# sandbox.net
KiCad netlist of a schematic drawn in EAGLE
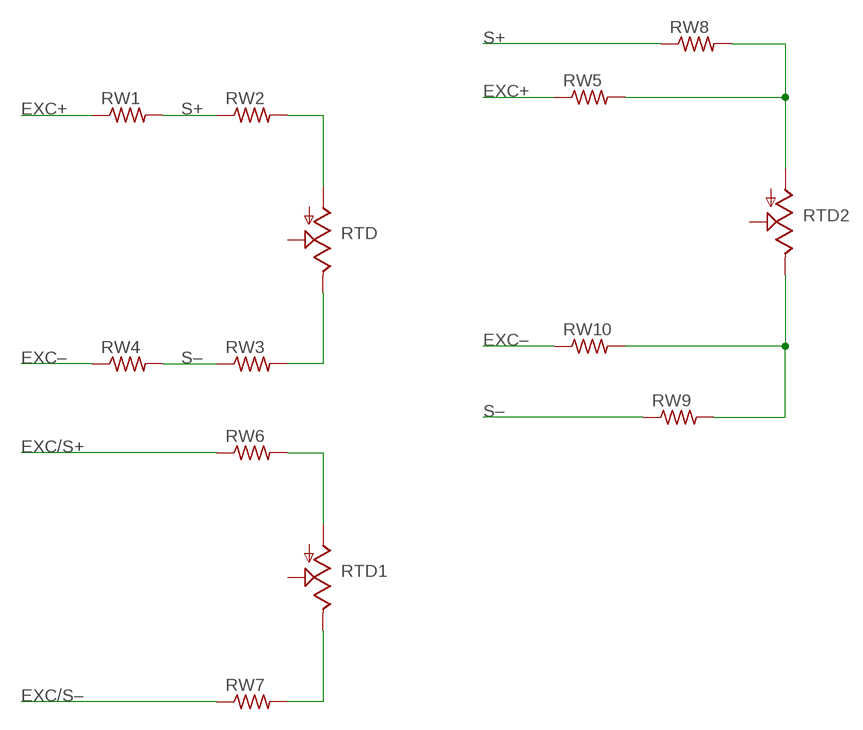
[diagram p0: schematic, sheet 1]

(export (version "E")
  (design (tool "Eeschema 10.0.6"))
  (components
    (comp (ref "RTD")
      (value "TRIM_US-3223G")
      (footprint "eagle-import:3223G")
      (libsource (lib "eagle-import") (part "TRIM_US-3223G"))
    )
    (comp (ref "RTD1")
      (value "TRIM_US-3223G")
      (footprint "eagle-import:3223G")
      (libsource (lib "eagle-import") (part "TRIM_US-3223G"))
    )
    (comp (ref "RTD2")
      (value "TRIM_US-3223G")
      (footprint "eagle-import:3223G")
      (libsource (lib "eagle-import") (part "TRIM_US-3223G"))
    )
    (comp (ref "RW1")
      (value "R-US_R0603")
      (footprint "eagle-import:R0603")
      (libsource (lib "eagle-import") (part "R-US_R0603"))
    )
    (comp (ref "RW2")
      (value "R-US_R0603")
      (footprint "eagle-import:R0603")
      (libsource (lib "eagle-import") (part "R-US_R0603"))
    )
    (comp (ref "RW3")
      (value "R-US_R0603")
      (footprint "eagle-import:R0603")
      (libsource (lib "eagle-import") (part "R-US_R0603"))
    )
    (comp (ref "RW4")
      (value "R-US_R0603")
      (footprint "eagle-import:R0603")
      (libsource (lib "eagle-import") (part "R-US_R0603"))
    )
    (comp (ref "RW5")
      (value "R-US_R0603")
      (footprint "eagle-import:R0603")
      (libsource (lib "eagle-import") (part "R-US_R0603"))
    )
    (comp (ref "RW6")
      (value "R-US_R0603")
      (footprint "eagle-import:R0603")
      (libsource (lib "eagle-import") (part "R-US_R0603"))
    )
    (comp (ref "RW7")
      (value "R-US_R0603")
      (footprint "eagle-import:R0603")
      (libsource (lib "eagle-import") (part "R-US_R0603"))
    )
    (comp (ref "RW8")
      (value "R-US_R0603")
      (footprint "eagle-import:R0603")
      (libsource (lib "eagle-import") (part "R-US_R0603"))
    )
    (comp (ref "RW9")
      (value "R-US_R0603")
      (footprint "eagle-import:R0603")
      (libsource (lib "eagle-import") (part "R-US_R0603"))
    )
    (comp (ref "RW10")
      (value "R-US_R0603")
      (footprint "eagle-import:R0603")
      (libsource (lib "eagle-import") (part "R-US_R0603"))
    )
  )
  (nets
    (net (code "1") (name "/EXC+") (class "Default")
      (node (ref "RW1") (pin "1") (pinfunction "1_1") (pintype "passive"))
      (node (ref "RW5") (pin "1") (pinfunction "1_1") (pintype "passive"))
    )
    (net (code "2") (name "/EXC{slash}S+") (class "Default")
      (node (ref "RW6") (pin "1") (pinfunction "1_1") (pintype "passive"))
    )
    (net (code "3") (name "/EXC{slash}S–") (class "Default")
      (node (ref "RW7") (pin "1") (pinfunction "1_1") (pintype "passive"))
    )
    (net (code "4") (name "/EXC–") (class "Default")
      (node (ref "RW10") (pin "1") (pinfunction "1_1") (pintype "passive"))
      (node (ref "RW4") (pin "1") (pinfunction "1_1") (pintype "passive"))
    )
    (net (code "5") (name "/S+") (class "Default")
      (node (ref "RW1") (pin "2") (pinfunction "2_2") (pintype "passive"))
      (node (ref "RW2") (pin "1") (pinfunction "1_1") (pintype "passive"))
      (node (ref "RW8") (pin "1") (pinfunction "1_1") (pintype "passive"))
    )
    (net (code "6") (name "/S–") (class "Default")
      (node (ref "RW3") (pin "1") (pinfunction "1_1") (pintype "passive"))
      (node (ref "RW4") (pin "2") (pinfunction "2_2") (pintype "passive"))
      (node (ref "RW9") (pin "1") (pinfunction "1_1") (pintype "passive"))
    )
    (net (code "7") (name "Net-(RTD-A)") (class "Default")
      (node (ref "RTD") (pin "1") (pinfunction "A_1") (pintype "passive"))
      (node (ref "RW2") (pin "2") (pinfunction "2_2") (pintype "passive"))
    )
    (net (code "8") (name "Net-(RTD-E)") (class "Default")
      (node (ref "RTD") (pin "3") (pinfunction "E_3") (pintype "passive"))
      (node (ref "RW3") (pin "2") (pinfunction "2_2") (pintype "passive"))
    )
    (net (code "9") (name "Net-(RTD1-A)") (class "Default")
      (node (ref "RTD1") (pin "1") (pinfunction "A_1") (pintype "passive"))
      (node (ref "RW6") (pin "2") (pinfunction "2_2") (pintype "passive"))
    )
    (net (code "10") (name "Net-(RTD1-E)") (class "Default")
      (node (ref "RTD1") (pin "3") (pinfunction "E_3") (pintype "passive"))
      (node (ref "RW7") (pin "2") (pinfunction "2_2") (pintype "passive"))
    )
    (net (code "11") (name "Net-(RTD2-A)") (class "Default")
      (node (ref "RTD2") (pin "1") (pinfunction "A_1") (pintype "passive"))
      (node (ref "RW5") (pin "2") (pinfunction "2_2") (pintype "passive"))
      (node (ref "RW8") (pin "2") (pinfunction "2_2") (pintype "passive"))
    )
    (net (code "12") (name "Net-(RTD2-E)") (class "Default")
      (node (ref "RTD2") (pin "3") (pinfunction "E_3") (pintype "passive"))
      (node (ref "RW10") (pin "2") (pinfunction "2_2") (pintype "passive"))
      (node (ref "RW9") (pin "2") (pinfunction "2_2") (pintype "passive"))
    )
    (net (code "13") (name "unconnected-(RTD-S-Pad2)") (class "Default")
      (node (ref "RTD") (pin "2") (pinfunction "S_2") (pintype "passive"))
    )
    (net (code "14") (name "unconnected-(RTD1-S-Pad2)") (class "Default")
      (node (ref "RTD1") (pin "2") (pinfunction "S_2") (pintype "passive"))
    )
    (net (code "15") (name "unconnected-(RTD2-S-Pad2)") (class "Default")
      (node (ref "RTD2") (pin "2") (pinfunction "S_2") (pintype "passive"))
    )
  )
)
